# programmer.net
KiCad netlist of a schematic drawn in EAGLE
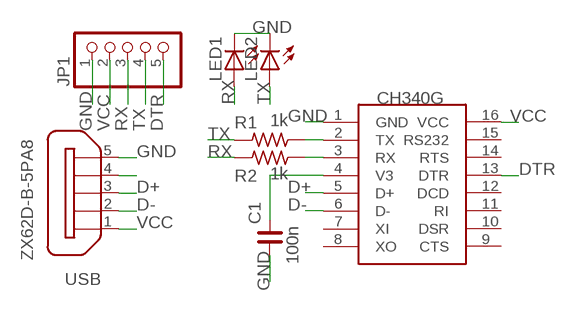
[diagram p0: schematic, sheet 1]

(export (version "E")
  (design (tool "Eeschema 10.0.6"))
  (components
    (comp (ref "C1")
      (value "100n")
      (footprint "eagle-import:C2012")
      (libsource (lib "eagle-import") (part "C_2012"))
    )
    (comp (ref "JP1")
      (value "PINHD-1X5")
      (footprint "eagle-import:1X05")
      (libsource (lib "eagle-import") (part "PINHD-1X5"))
    )
    (comp (ref "LED1")
      (value "LEDCHIP-LED0805")
      (footprint "eagle-import:CHIP-LED0805")
      (libsource (lib "eagle-import") (part "LEDCHIP-LED0805"))
    )
    (comp (ref "LED2")
      (value "LEDCHIP-LED0805")
      (footprint "eagle-import:CHIP-LED0805")
      (libsource (lib "eagle-import") (part "LEDCHIP-LED0805"))
    )
    (comp (ref "R1")
      (value "1k")
      (footprint "eagle-import:R2012")
      (libsource (lib "eagle-import") (part "R_2012"))
    )
    (comp (ref "R2")
      (value "1k")
      (footprint "eagle-import:R2012")
      (libsource (lib "eagle-import") (part "R_2012"))
    )
    (comp (ref "U$1")
      (value "CH340G")
      (footprint "eagle-import:SOIC16")
      (libsource (lib "eagle-import") (part "CH340G"))
    )
    (comp (ref "USB")
      (value "ZX62D-B-5PA8")
      (footprint "eagle-import:ZX62D-B-5PA8")
      (fields (field (name "MF") "Hirose"))
      (libsource (lib "eagle-import") (part "ZX62D-B-5PA8"))
    )
  )
  (nets
    (net (code "1") (name "/D+") (class "Default")
      (node (ref "U$1") (pin "5") (pinfunction "D+_5") (pintype "bidirectional"))
      (node (ref "USB") (pin "3") (pinfunction "3_3") (pintype "passive"))
    )
    (net (code "2") (name "/D-") (class "Default")
      (node (ref "U$1") (pin "6") (pinfunction "D-_6") (pintype "bidirectional"))
      (node (ref "USB") (pin "2") (pinfunction "2_2") (pintype "passive"))
    )
    (net (code "3") (name "/DTR") (class "Default")
      (node (ref "JP1") (pin "5") (pinfunction "5_5") (pintype "passive"))
      (node (ref "U$1") (pin "13") (pinfunction "DTR_13") (pintype "bidirectional"))
    )
    (net (code "4") (name "/GND") (class "Default")
      (node (ref "C1") (pin "1") (pinfunction "1_1") (pintype "passive"))
      (node (ref "JP1") (pin "1") (pinfunction "1_1") (pintype "passive"))
      (node (ref "LED1") (pin "C") (pinfunction "C_C") (pintype "passive"))
      (node (ref "LED2") (pin "C") (pinfunction "C_C") (pintype "passive"))
      (node (ref "U$1") (pin "1") (pinfunction "GND_1") (pintype "bidirectional"))
      (node (ref "USB") (pin "5") (pinfunction "5_5") (pintype "passive"))
    )
    (net (code "5") (name "/RX") (class "Default")
      (node (ref "JP1") (pin "3") (pinfunction "3_3") (pintype "passive"))
      (node (ref "LED1") (pin "A") (pinfunction "A_A") (pintype "passive"))
      (node (ref "R2") (pin "1") (pinfunction "1_1") (pintype "passive"))
    )
    (net (code "6") (name "/TX") (class "Default")
      (node (ref "JP1") (pin "4") (pinfunction "4_4") (pintype "passive"))
      (node (ref "LED2") (pin "A") (pinfunction "A_A") (pintype "passive"))
      (node (ref "R1") (pin "1") (pinfunction "1_1") (pintype "passive"))
    )
    (net (code "7") (name "/VCC") (class "Default")
      (node (ref "JP1") (pin "2") (pinfunction "2_2") (pintype "passive"))
      (node (ref "U$1") (pin "16") (pinfunction "VCC_16") (pintype "bidirectional"))
      (node (ref "USB") (pin "1") (pinfunction "1_1") (pintype "passive"))
    )
    (net (code "8") (name "Net-(U$1-RX)") (class "Default")
      (node (ref "R2") (pin "2") (pinfunction "2_2") (pintype "passive"))
      (node (ref "U$1") (pin "3") (pinfunction "RX_3") (pintype "bidirectional"))
    )
    (net (code "9") (name "Net-(U$1-TX)") (class "Default")
      (node (ref "R1") (pin "2") (pinfunction "2_2") (pintype "passive"))
      (node (ref "U$1") (pin "2") (pinfunction "TX_2") (pintype "bidirectional"))
    )
    (net (code "10") (name "Net-(U$1-V3)") (class "Default")
      (node (ref "C1") (pin "2") (pinfunction "2_2") (pintype "passive"))
      (node (ref "U$1") (pin "4") (pinfunction "V3_4") (pintype "bidirectional"))
    )
    (net (code "11") (name "unconnected-(U$1-CTS-Pad9)") (class "Default")
      (node (ref "U$1") (pin "9") (pinfunction "CTS_9") (pintype "bidirectional"))
    )
    (net (code "12") (name "unconnected-(U$1-DCD-Pad12)") (class "Default")
      (node (ref "U$1") (pin "12") (pinfunction "DCD_12") (pintype "bidirectional"))
    )
    (net (code "13") (name "unconnected-(U$1-DSR-Pad10)") (class "Default")
      (node (ref "U$1") (pin "10") (pinfunction "DSR_10") (pintype "bidirectional"))
    )
    (net (code "14") (name "unconnected-(U$1-RI-Pad11)") (class "Default")
      (node (ref "U$1") (pin "11") (pinfunction "RI_11") (pintype "bidirectional"))
    )
    (net (code "15") (name "unconnected-(U$1-RS232-Pad15)") (class "Default")
      (node (ref "U$1") (pin "15") (pinfunction "RS232_15") (pintype "bidirectional"))
    )
    (net (code "16") (name "unconnected-(U$1-RTS-Pad14)") (class "Default")
      (node (ref "U$1") (pin "14") (pinfunction "RTS_14") (pintype "bidirectional"))
    )
    (net (code "17") (name "unconnected-(U$1-XI-Pad7)") (class "Default")
      (node (ref "U$1") (pin "7") (pinfunction "XI_7") (pintype "bidirectional"))
    )
    (net (code "18") (name "unconnected-(U$1-XO-Pad8)") (class "Default")
      (node (ref "U$1") (pin "8") (pinfunction "XO_8") (pintype "bidirectional"))
    )
    (net (code "19") (name "unconnected-(USB-Pad4)") (class "Default")
      (node (ref "USB") (pin "4") (pinfunction "4_4") (pintype "passive"))
    )
  )
)
